# BoardB-USB.net
KiCad netlist of a schematic drawn in Altium Designer
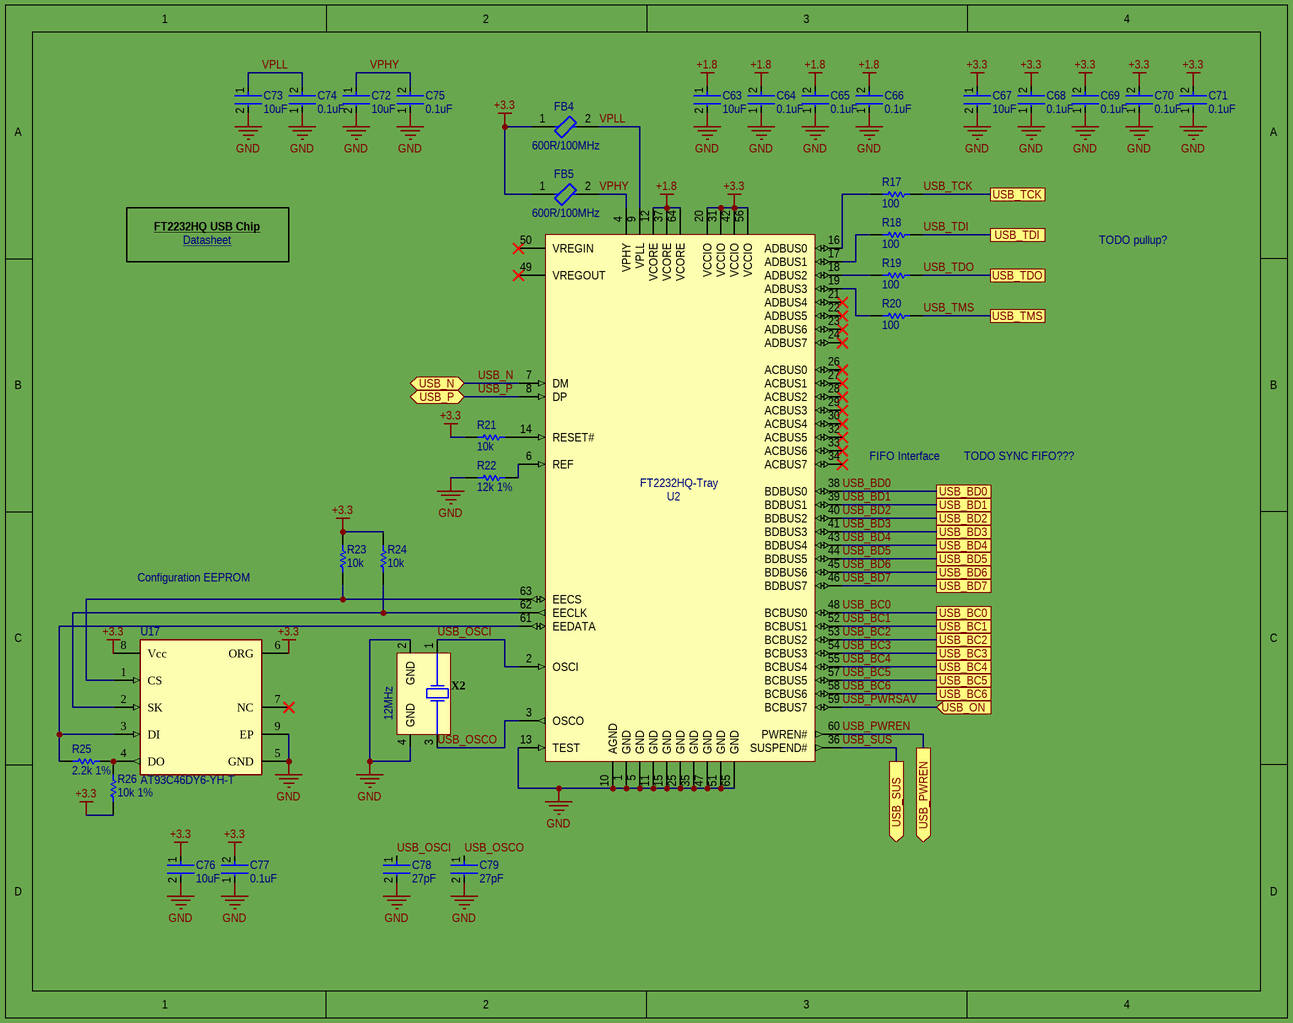
[diagram p0: BoardB-USB.SchDoc]

(export (version "E")
  (design (tool "Eeschema 10.0.6"))
  (components
    (comp (ref "C63")
      (value "10uF")
      (footprint "FP-CL05A106MP5NUNC-IPC_C")
      (description "CAP CER 10UF 10V X5R 0402")
      (fields
        (field (name "OCTOPART") "https://octopart.com/cl05a106mp5nunc-samsung-22457395")
        (field (name "TOLERANCE") "20%")
      )
      (libsource (lib "Altium Content Vault") (part "b4654b650e69147ec39a6b967a45e02"))
    )
    (comp (ref "C64")
      (value "0.1uF")
      (footprint "FP-GRM15-IPC_C")
      (description "CAP CER 0.1UF 16V X7R 0402")
      (fields (field (name "MANUFACTURER PART NUMBER") "GRM155R71C104KA88D") (field (name "TOLERANCE") "10%"))
      (libsource (lib "Altium Content Vault") (part "236180d848d6139a670b325ea6854c9"))
    )
    (comp (ref "C65")
      (value "0.1uF")
      (footprint "FP-GRM15-IPC_C")
      (description "CAP CER 0.1UF 16V X7R 0402")
      (fields (field (name "MANUFACTURER PART NUMBER") "GRM155R71C104KA88D") (field (name "TOLERANCE") "10%"))
      (libsource (lib "Altium Content Vault") (part "236180d848d6139a670b325ea6854c9"))
    )
    (comp (ref "C66")
      (value "0.1uF")
      (footprint "FP-GRM15-IPC_C")
      (description "CAP CER 0.1UF 16V X7R 0402")
      (fields (field (name "MANUFACTURER PART NUMBER") "GRM155R71C104KA88D") (field (name "TOLERANCE") "10%"))
      (libsource (lib "Altium Content Vault") (part "236180d848d6139a670b325ea6854c9"))
    )
    (comp (ref "C67")
      (value "10uF")
      (footprint "FP-CL05A106MP5NUNC-IPC_C")
      (description "CAP CER 10UF 10V X5R 0402")
      (fields
        (field (name "OCTOPART") "https://octopart.com/cl05a106mp5nunc-samsung-22457395")
        (field (name "TOLERANCE") "20%")
      )
      (libsource (lib "Altium Content Vault") (part "b4654b650e69147ec39a6b967a45e02"))
    )
    (comp (ref "C68")
      (value "0.1uF")
      (footprint "FP-GRM15-IPC_C")
      (description "CAP CER 0.1UF 16V X7R 0402")
      (fields (field (name "MANUFACTURER PART NUMBER") "GRM155R71C104KA88D") (field (name "TOLERANCE") "10%"))
      (libsource (lib "Altium Content Vault") (part "236180d848d6139a670b325ea6854c9"))
    )
    (comp (ref "C69")
      (value "0.1uF")
      (footprint "FP-GRM15-IPC_C")
      (description "CAP CER 0.1UF 16V X7R 0402")
      (fields (field (name "MANUFACTURER PART NUMBER") "GRM155R71C104KA88D") (field (name "TOLERANCE") "10%"))
      (libsource (lib "Altium Content Vault") (part "236180d848d6139a670b325ea6854c9"))
    )
    (comp (ref "C70")
      (value "0.1uF")
      (footprint "FP-GRM15-IPC_C")
      (description "CAP CER 0.1UF 16V X7R 0402")
      (fields (field (name "MANUFACTURER PART NUMBER") "GRM155R71C104KA88D") (field (name "TOLERANCE") "10%"))
      (libsource (lib "Altium Content Vault") (part "236180d848d6139a670b325ea6854c9"))
    )
    (comp (ref "C71")
      (value "0.1uF")
      (footprint "FP-GRM15-IPC_C")
      (description "CAP CER 0.1UF 16V X7R 0402")
      (fields (field (name "MANUFACTURER PART NUMBER") "GRM155R71C104KA88D") (field (name "TOLERANCE") "10%"))
      (libsource (lib "Altium Content Vault") (part "236180d848d6139a670b325ea6854c9"))
    )
    (comp (ref "C72")
      (value "10uF")
      (footprint "FP-CL05A106MP5NUNC-IPC_C")
      (description "CAP CER 10UF 10V X5R 0402")
      (fields
        (field (name "OCTOPART") "https://octopart.com/cl05a106mp5nunc-samsung-22457395")
        (field (name "TOLERANCE") "20%")
      )
      (libsource (lib "Altium Content Vault") (part "b4654b650e69147ec39a6b967a45e02"))
    )
    (comp (ref "C73")
      (value "10uF")
      (footprint "FP-CL05A106MP5NUNC-IPC_C")
      (description "CAP CER 10UF 10V X5R 0402")
      (fields
        (field (name "OCTOPART") "https://octopart.com/cl05a106mp5nunc-samsung-22457395")
        (field (name "TOLERANCE") "20%")
      )
      (libsource (lib "Altium Content Vault") (part "b4654b650e69147ec39a6b967a45e02"))
    )
    (comp (ref "C74")
      (value "0.1uF")
      (footprint "FP-GRM15-IPC_C")
      (description "CAP CER 0.1UF 16V X7R 0402")
      (fields (field (name "MANUFACTURER PART NUMBER") "GRM155R71C104KA88D") (field (name "TOLERANCE") "10%"))
      (libsource (lib "Altium Content Vault") (part "236180d848d6139a670b325ea6854c9"))
    )
    (comp (ref "C75")
      (value "0.1uF")
      (footprint "FP-GRM15-IPC_C")
      (description "CAP CER 0.1UF 16V X7R 0402")
      (fields (field (name "MANUFACTURER PART NUMBER") "GRM155R71C104KA88D") (field (name "TOLERANCE") "10%"))
      (libsource (lib "Altium Content Vault") (part "236180d848d6139a670b325ea6854c9"))
    )
    (comp (ref "C76")
      (value "10uF")
      (footprint "FP-CL05A106MP5NUNC-IPC_C")
      (description "CAP CER 10UF 10V X5R 0402")
      (fields
        (field (name "OCTOPART") "https://octopart.com/cl05a106mp5nunc-samsung-22457395")
        (field (name "TOLERANCE") "20%")
      )
      (libsource (lib "Altium Content Vault") (part "b4654b650e69147ec39a6b967a45e02"))
    )
    (comp (ref "C77")
      (value "0.1uF")
      (footprint "FP-GRM15-IPC_C")
      (description "CAP CER 0.1UF 16V X7R 0402")
      (fields (field (name "MANUFACTURER PART NUMBER") "GRM155R71C104KA88D") (field (name "TOLERANCE") "10%"))
      (libsource (lib "Altium Content Vault") (part "236180d848d6139a670b325ea6854c9"))
    )
    (comp (ref "C78")
      (value "27pF")
      (footprint "FP-C0402-BB-MFG")
      (description "CAP CER 27PF 50V C0G/NP0 0402")
      (fields (field (name "MANUFACTURER") "Kemet") (field (name "TOLERANCE") "0.05"))
      (libsource (lib "Altium Content Vault") (part "b4654b650e69147ec39a6b967a45e02"))
    )
    (comp (ref "C79")
      (value "27pF")
      (footprint "FP-C0402-BB-MFG")
      (description "CAP CER 27PF 50V C0G/NP0 0402")
      (fields (field (name "MANUFACTURER") "Kemet") (field (name "TOLERANCE") "0.05"))
      (libsource (lib "Altium Content Vault") (part "b4654b650e69147ec39a6b967a45e02"))
    )
    (comp (ref "FB4")
      (value "600R/100MHz")
      (footprint "FP-BLM18-0_15-t0_8-MFG")
      (description "Chip Ferrite Bead, 0603, 600Ω @ 100MHz, 0.38Ω, 25%, 500mA")
      (fields (field (name "TOLERANCE") "25%"))
      (libsource (lib "Altium Content Vault") (part "5f30dd21d616792df468990f7003faa"))
    )
    (comp (ref "FB5")
      (value "600R/100MHz")
      (footprint "FP-BLM18-0_15-t0_8-MFG")
      (description "Chip Ferrite Bead, 0603, 600Ω @ 100MHz, 0.38Ω, 25%, 500mA")
      (fields (field (name "TOLERANCE") "25%"))
      (libsource (lib "Altium Content Vault") (part "5f30dd21d616792df468990f7003faa"))
    )
    (comp (ref "R17")
      (value "100")
      (footprint "RESC1005X40X25LL05T10")
      (fields (field (name "PART NUMBER") "RC0402FR-07100RL") (field (name "MANUFACTURER") "Yageo / Phycomp"))
      (libsource (lib "Altium Content Vault") (part "RES"))
    )
    (comp (ref "R18")
      (value "100")
      (footprint "RESC1005X40X25LL05T10")
      (fields (field (name "PART NUMBER") "RC0402FR-07100RL") (field (name "MANUFACTURER") "Yageo / Phycomp"))
      (libsource (lib "Altium Content Vault") (part "RES"))
    )
    (comp (ref "R19")
      (value "100")
      (footprint "RESC1005X40X25LL05T10")
      (fields (field (name "PART NUMBER") "RC0402FR-07100RL") (field (name "MANUFACTURER") "Yageo / Phycomp"))
      (libsource (lib "Altium Content Vault") (part "RES"))
    )
    (comp (ref "R20")
      (value "100")
      (footprint "RESC1005X40X25LL05T10")
      (fields (field (name "PART NUMBER") "RC0402FR-07100RL") (field (name "MANUFACTURER") "Yageo / Phycomp"))
      (libsource (lib "Altium Content Vault") (part "RES"))
    )
    (comp (ref "R21")
      (value "10k")
      (footprint "RESC1005X40X25LL05T05")
      (description "Chip Resistor, 10 KOhm, +/- 1%, 0.1 W, -55 to 155 degC, 0402 (1005 Metric), RoHS, Tape and Reel")
      (fields (field (name "TOLERANCE") "1%") (field (name "MANUFACTURER") "Panasonic"))
      (libsource (lib "Altium Content Vault") (part "RES-2"))
    )
    (comp (ref "R22")
      (value "12k 1%")
      (footprint "RESC1005X40X25LL05T05")
      (description "Chip Resistor, 12 KOhm, +/- 1%, 0.1 W, -55 to 155 degC, 0402 (1005 Metric), RoHS, Tape and Reel")
      (fields (field (name "TOLERANCE") "1%") (field (name "PARTNUMBER") "ERJ-2RKF1202X"))
      (libsource (lib "Altium Content Vault") (part "RES-2"))
    )
    (comp (ref "R23")
      (value "10k")
      (footprint "RESC1005X40X25LL05T05")
      (description "Chip Resistor, 10 KOhm, +/- 1%, 0.1 W, -55 to 155 degC, 0402 (1005 Metric), RoHS, Tape and Reel")
      (fields (field (name "TOLERANCE") "1%") (field (name "MANUFACTURER") "Panasonic"))
      (libsource (lib "Altium Content Vault") (part "RES-2"))
    )
    (comp (ref "R24")
      (value "10k")
      (footprint "RESC1005X40X25LL05T05")
      (description "Chip Resistor, 10 KOhm, +/- 1%, 0.1 W, -55 to 155 degC, 0402 (1005 Metric), RoHS, Tape and Reel")
      (fields (field (name "TOLERANCE") "1%") (field (name "MANUFACTURER") "Panasonic"))
      (libsource (lib "Altium Content Vault") (part "RES-2"))
    )
    (comp (ref "R25")
      (value "2.2k 1%")
      (footprint "RESC1005X40X25NL05T10")
      (fields (field (name "MANUFACTURER") "Yageo / Phycomp") (field (name "PART NUMBER") "RC0402FR-072K2L"))
      (libsource (lib "Altium Content Vault") (part "RES"))
    )
    (comp (ref "R26")
      (value "10k 1%")
      (footprint "RESC1005X40X25LL05T05")
      (description "Chip Resistor, 10 KOhm, +/- 1%, 0.1 W, -55 to 155 degC, 0402 (1005 Metric), RoHS, Tape and Reel")
      (fields (field (name "TOLERANCE") "1%") (field (name "MANUFACTURER") "Panasonic"))
      (libsource (lib "Altium Content Vault") (part "RES-2"))
    )
    (comp (ref "U2")
      (value "FT2232HQ-Tray")
      (footprint "QFN64_2_N")
      (description "Dual High Speed USB To Multipurpose UART/FIFO IC, 64-pin QFN, Tray")
      (fields (field (name "MANUFACTURER") "FTDI"))
      (libsource (lib "Altium Content Vault") (part "COM-UART-FT2232H-QFN64"))
    )
    (comp (ref "U17")
      (value "AT93C46DY6-YH-T")
      (footprint "FP-C04-21355-Q4B-IPC_C")
      (description "IC EEPROM 1KBIT SPI 8MINI MAP")
      (libsource (lib "Altium Content Vault") (part "38d5b16ef365a7a64ac37fa7d10f17c"))
    )
    (comp (ref "X2")
      (value "ABM8G-12.000MHZ-4Y-T3")
      (footprint "ABM8G-12.000MHZ-4Y-T3")
      (description "ABRACON - ABM8G-12.000MHZ-4Y-T3 - CRYSTAL, 12MHZ, 10PF, 3.2 X 2.5MM")
      (fields (field (name "MANUFACTURER") "Abracon"))
      (libsource (lib "Virtex") (part "ABM8G-12.000MHZ-4Y-T3"))
    )
  )
  (nets
    (net (code "1") (name "+1.8") (class "Default")
      (node (ref "C63") (pin "1") (pinfunction "1_1") (pintype "passive"))
      (node (ref "C64") (pin "2") (pinfunction "2_2") (pintype "passive"))
      (node (ref "C65") (pin "2") (pinfunction "2_2") (pintype "passive"))
      (node (ref "C66") (pin "2") (pinfunction "2_2") (pintype "passive"))
      (node (ref "U2") (pin "12") (pinfunction "VCORE_12") (pintype "power_in"))
      (node (ref "U2") (pin "37") (pinfunction "VCORE_37") (pintype "power_in"))
      (node (ref "U2") (pin "64") (pinfunction "VCORE_64") (pintype "power_in"))
    )
    (net (code "2") (name "+3.3") (class "Default")
      (node (ref "C67") (pin "1") (pinfunction "1_1") (pintype "passive"))
      (node (ref "C68") (pin "2") (pinfunction "2_2") (pintype "passive"))
      (node (ref "C69") (pin "2") (pinfunction "2_2") (pintype "passive"))
      (node (ref "C70") (pin "2") (pinfunction "2_2") (pintype "passive"))
      (node (ref "C71") (pin "2") (pinfunction "2_2") (pintype "passive"))
      (node (ref "C76") (pin "1") (pinfunction "1_1") (pintype "passive"))
      (node (ref "C77") (pin "2") (pinfunction "2_2") (pintype "passive"))
      (node (ref "FB4") (pin "1") (pinfunction "1_1") (pintype "passive"))
      (node (ref "FB5") (pin "1") (pinfunction "1_1") (pintype "passive"))
      (node (ref "R21") (pin "2") (pinfunction "2_2") (pintype "passive"))
      (node (ref "R23") (pin "2") (pinfunction "2_2") (pintype "passive"))
      (node (ref "R24") (pin "2") (pinfunction "2_2") (pintype "passive"))
      (node (ref "R26") (pin "1") (pinfunction "1_1") (pintype "passive"))
      (node (ref "U17") (pin "6") (pinfunction "ORG_6") (pintype "passive"))
      (node (ref "U17") (pin "8") (pinfunction "Vcc_8") (pintype "power_in"))
      (node (ref "U2") (pin "20") (pinfunction "VCCIO_20") (pintype "power_in"))
      (node (ref "U2") (pin "31") (pinfunction "VCCIO_31") (pintype "power_in"))
      (node (ref "U2") (pin "42") (pinfunction "VCCIO_42") (pintype "power_in"))
      (node (ref "U2") (pin "56") (pinfunction "VCCIO_56") (pintype "power_in"))
    )
    (net (code "3") (name "/USB_BC0") (class "Default")
      (node (ref "U2") (pin "48") (pinfunction "BCBUS0_48") (pintype "bidirectional"))
    )
    (net (code "4") (name "/USB_BC1") (class "Default")
      (node (ref "U2") (pin "52") (pinfunction "BCBUS1_52") (pintype "bidirectional"))
    )
    (net (code "5") (name "/USB_BC2") (class "Default")
      (node (ref "U2") (pin "53") (pinfunction "BCBUS2_53") (pintype "bidirectional"))
    )
    (net (code "6") (name "/USB_BC3") (class "Default")
      (node (ref "U2") (pin "54") (pinfunction "BCBUS3_54") (pintype "bidirectional"))
    )
    (net (code "7") (name "/USB_BC4") (class "Default")
      (node (ref "U2") (pin "55") (pinfunction "BCBUS4_55") (pintype "bidirectional"))
    )
    (net (code "8") (name "/USB_BC5") (class "Default")
      (node (ref "U2") (pin "57") (pinfunction "BCBUS5_57") (pintype "bidirectional"))
    )
    (net (code "9") (name "/USB_BC6") (class "Default")
      (node (ref "U2") (pin "58") (pinfunction "BCBUS6_58") (pintype "bidirectional"))
    )
    (net (code "10") (name "/USB_BD0") (class "Default")
      (node (ref "U2") (pin "38") (pinfunction "BDBUS0_38") (pintype "bidirectional"))
    )
    (net (code "11") (name "/USB_BD1") (class "Default")
      (node (ref "U2") (pin "39") (pinfunction "BDBUS1_39") (pintype "bidirectional"))
    )
    (net (code "12") (name "/USB_BD2") (class "Default")
      (node (ref "U2") (pin "40") (pinfunction "BDBUS2_40") (pintype "bidirectional"))
    )
    (net (code "13") (name "/USB_BD3") (class "Default")
      (node (ref "U2") (pin "41") (pinfunction "BDBUS3_41") (pintype "bidirectional"))
    )
    (net (code "14") (name "/USB_BD4") (class "Default")
      (node (ref "U2") (pin "43") (pinfunction "BDBUS4_43") (pintype "bidirectional"))
    )
    (net (code "15") (name "/USB_BD5") (class "Default")
      (node (ref "U2") (pin "44") (pinfunction "BDBUS5_44") (pintype "bidirectional"))
    )
    (net (code "16") (name "/USB_BD6") (class "Default")
      (node (ref "U2") (pin "45") (pinfunction "BDBUS6_45") (pintype "bidirectional"))
    )
    (net (code "17") (name "/USB_BD7") (class "Default")
      (node (ref "U2") (pin "46") (pinfunction "BDBUS7_46") (pintype "bidirectional"))
    )
    (net (code "18") (name "/USB_N") (class "Default")
      (node (ref "U2") (pin "7") (pinfunction "DM_7") (pintype "input"))
    )
    (net (code "19") (name "/USB_OSCI") (class "Default")
      (node (ref "C78") (pin "1") (pinfunction "1_1") (pintype "passive"))
      (node (ref "U2") (pin "2") (pinfunction "OSCI_2") (pintype "input"))
      (node (ref "X2") (pin "1") (pintype "passive"))
    )
    (net (code "20") (name "/USB_OSCO") (class "Default")
      (node (ref "C79") (pin "1") (pinfunction "1_1") (pintype "passive"))
      (node (ref "U2") (pin "3") (pinfunction "OSCO_3") (pintype "output"))
      (node (ref "X2") (pin "3") (pintype "passive"))
    )
    (net (code "21") (name "/USB_P") (class "Default")
      (node (ref "U2") (pin "8") (pinfunction "DP_8") (pintype "input"))
    )
    (net (code "22") (name "/USB_PWREN") (class "Default")
      (node (ref "U2") (pin "60") (pinfunction "PWREN#_60") (pintype "output"))
    )
    (net (code "23") (name "/USB_PWRSAV") (class "Default")
      (node (ref "U2") (pin "59") (pinfunction "BCBUS7_59") (pintype "bidirectional"))
    )
    (net (code "24") (name "/USB_SUS") (class "Default")
      (node (ref "U2") (pin "36") (pinfunction "SUSPEND#_36") (pintype "output"))
    )
    (net (code "25") (name "/USB_TCK") (class "Default")
      (node (ref "R17") (pin "2") (pinfunction "2_2") (pintype "passive"))
    )
    (net (code "26") (name "/USB_TDI") (class "Default")
      (node (ref "R18") (pin "2") (pinfunction "2_2") (pintype "passive"))
    )
    (net (code "27") (name "/USB_TDO") (class "Default")
      (node (ref "R19") (pin "2") (pinfunction "2_2") (pintype "passive"))
    )
    (net (code "28") (name "/USB_TMS") (class "Default")
      (node (ref "R20") (pin "2") (pinfunction "2_2") (pintype "passive"))
    )
    (net (code "29") (name "/VPHY") (class "Default")
      (node (ref "C72") (pin "1") (pinfunction "1_1") (pintype "passive"))
      (node (ref "C75") (pin "2") (pinfunction "2_2") (pintype "passive"))
      (node (ref "FB5") (pin "2") (pinfunction "2_2") (pintype "passive"))
      (node (ref "U2") (pin "4") (pinfunction "VPHY_4") (pintype "power_in"))
    )
    (net (code "30") (name "/VPLL") (class "Default")
      (node (ref "C73") (pin "1") (pinfunction "1_1") (pintype "passive"))
      (node (ref "C74") (pin "2") (pinfunction "2_2") (pintype "passive"))
      (node (ref "FB4") (pin "2") (pinfunction "2_2") (pintype "passive"))
      (node (ref "U2") (pin "9") (pinfunction "VPLL_9") (pintype "power_in"))
    )
    (net (code "31") (name "GND") (class "Default")
      (node (ref "C63") (pin "2") (pinfunction "2_2") (pintype "passive"))
      (node (ref "C64") (pin "1") (pinfunction "1_1") (pintype "passive"))
      (node (ref "C65") (pin "1") (pinfunction "1_1") (pintype "passive"))
      (node (ref "C66") (pin "1") (pinfunction "1_1") (pintype "passive"))
      (node (ref "C67") (pin "2") (pinfunction "2_2") (pintype "passive"))
      (node (ref "C68") (pin "1") (pinfunction "1_1") (pintype "passive"))
      (node (ref "C69") (pin "1") (pinfunction "1_1") (pintype "passive"))
      (node (ref "C70") (pin "1") (pinfunction "1_1") (pintype "passive"))
      (node (ref "C71") (pin "1") (pinfunction "1_1") (pintype "passive"))
      (node (ref "C72") (pin "2") (pinfunction "2_2") (pintype "passive"))
      (node (ref "C73") (pin "2") (pinfunction "2_2") (pintype "passive"))
      (node (ref "C74") (pin "1") (pinfunction "1_1") (pintype "passive"))
      (node (ref "C75") (pin "1") (pinfunction "1_1") (pintype "passive"))
      (node (ref "C76") (pin "2") (pinfunction "2_2") (pintype "passive"))
      (node (ref "C77") (pin "1") (pinfunction "1_1") (pintype "passive"))
      (node (ref "C78") (pin "2") (pinfunction "2_2") (pintype "passive"))
      (node (ref "C79") (pin "2") (pinfunction "2_2") (pintype "passive"))
      (node (ref "R22") (pin "1") (pinfunction "1_1") (pintype "passive"))
      (node (ref "U17") (pin "5") (pinfunction "GND_5") (pintype "power_in"))
      (node (ref "U17") (pin "9") (pinfunction "EP_9") (pintype "passive"))
      (node (ref "U2") (pin "1") (pinfunction "GND_1") (pintype "power_in"))
      (node (ref "U2") (pin "10") (pinfunction "AGND_10") (pintype "power_in"))
      (node (ref "U2") (pin "11") (pinfunction "GND_11") (pintype "power_in"))
      (node (ref "U2") (pin "13") (pinfunction "TEST_13") (pintype "input"))
      (node (ref "U2") (pin "15") (pinfunction "GND_15") (pintype "power_in"))
      (node (ref "U2") (pin "25") (pinfunction "GND_25") (pintype "power_in"))
      (node (ref "U2") (pin "35") (pinfunction "GND_35") (pintype "power_in"))
      (node (ref "U2") (pin "47") (pinfunction "GND_47") (pintype "power_in"))
      (node (ref "U2") (pin "5") (pinfunction "GND_5") (pintype "power_in"))
      (node (ref "U2") (pin "51") (pinfunction "GND_51") (pintype "power_in"))
      (node (ref "U2") (pin "65") (pinfunction "GND_65") (pintype "power_in"))
      (node (ref "X2") (pin "2") (pinfunction "GND_2") (pintype "power_in"))
      (node (ref "X2") (pin "4") (pinfunction "GND_4") (pintype "power_in"))
    )
    (net (code "32") (name "Net-(U2-ADBUS0)") (class "Default")
      (node (ref "R17") (pin "1") (pinfunction "1_1") (pintype "passive"))
      (node (ref "U2") (pin "16") (pinfunction "ADBUS0_16") (pintype "bidirectional"))
    )
    (net (code "33") (name "Net-(U2-ADBUS1)") (class "Default")
      (node (ref "R18") (pin "1") (pinfunction "1_1") (pintype "passive"))
      (node (ref "U2") (pin "17") (pinfunction "ADBUS1_17") (pintype "bidirectional"))
    )
    (net (code "34") (name "Net-(U2-ADBUS2)") (class "Default")
      (node (ref "R19") (pin "1") (pinfunction "1_1") (pintype "passive"))
      (node (ref "U2") (pin "18") (pinfunction "ADBUS2_18") (pintype "bidirectional"))
    )
    (net (code "35") (name "Net-(U2-ADBUS3)") (class "Default")
      (node (ref "R20") (pin "1") (pinfunction "1_1") (pintype "passive"))
      (node (ref "U2") (pin "19") (pinfunction "ADBUS3_19") (pintype "bidirectional"))
    )
    (net (code "36") (name "Net-(U2-REF)") (class "Default")
      (node (ref "R22") (pin "2") (pinfunction "2_2") (pintype "passive"))
      (node (ref "U2") (pin "6") (pinfunction "REF_6") (pintype "input"))
    )
    (net (code "37") (name "Net-(U2-RESET#)") (class "Default")
      (node (ref "R21") (pin "1") (pinfunction "1_1") (pintype "passive"))
      (node (ref "U2") (pin "14") (pinfunction "RESET#_14") (pintype "input"))
    )
    (net (code "38") (name "Net-(U17-CS)") (class "Default")
      (node (ref "R23") (pin "1") (pinfunction "1_1") (pintype "passive"))
      (node (ref "U17") (pin "1") (pinfunction "CS_1") (pintype "input"))
      (node (ref "U2") (pin "63") (pinfunction "EECS_63") (pintype "bidirectional"))
    )
    (net (code "39") (name "Net-(U17-DI)") (class "Default")
      (node (ref "R25") (pin "1") (pinfunction "1_1") (pintype "passive"))
      (node (ref "U17") (pin "3") (pinfunction "DI_3") (pintype "input"))
      (node (ref "U2") (pin "61") (pinfunction "EEDATA_61") (pintype "bidirectional"))
    )
    (net (code "40") (name "Net-(U17-DO)") (class "Default")
      (node (ref "R25") (pin "2") (pinfunction "2_2") (pintype "passive"))
      (node (ref "R26") (pin "2") (pinfunction "2_2") (pintype "passive"))
      (node (ref "U17") (pin "4") (pinfunction "DO_4") (pintype "output"))
    )
    (net (code "41") (name "Net-(U17-SK)") (class "Default")
      (node (ref "R24") (pin "1") (pinfunction "1_1") (pintype "passive"))
      (node (ref "U17") (pin "2") (pinfunction "SK_2") (pintype "input"))
      (node (ref "U2") (pin "62") (pinfunction "EECLK_62") (pintype "output"))
    )
    (net (code "42") (name "unconnected-(U2-ACBUS0-Pad26)") (class "Default")
      (node (ref "U2") (pin "26") (pinfunction "ACBUS0_26") (pintype "bidirectional+no_connect"))
    )
    (net (code "43") (name "unconnected-(U2-ACBUS1-Pad27)") (class "Default")
      (node (ref "U2") (pin "27") (pinfunction "ACBUS1_27") (pintype "bidirectional+no_connect"))
    )
    (net (code "44") (name "unconnected-(U2-ACBUS2-Pad28)") (class "Default")
      (node (ref "U2") (pin "28") (pinfunction "ACBUS2_28") (pintype "bidirectional+no_connect"))
    )
    (net (code "45") (name "unconnected-(U2-ACBUS3-Pad29)") (class "Default")
      (node (ref "U2") (pin "29") (pinfunction "ACBUS3_29") (pintype "bidirectional+no_connect"))
    )
    (net (code "46") (name "unconnected-(U2-ACBUS4-Pad30)") (class "Default")
      (node (ref "U2") (pin "30") (pinfunction "ACBUS4_30") (pintype "bidirectional+no_connect"))
    )
    (net (code "47") (name "unconnected-(U2-ACBUS5-Pad32)") (class "Default")
      (node (ref "U2") (pin "32") (pinfunction "ACBUS5_32") (pintype "bidirectional+no_connect"))
    )
    (net (code "48") (name "unconnected-(U2-ACBUS6-Pad33)") (class "Default")
      (node (ref "U2") (pin "33") (pinfunction "ACBUS6_33") (pintype "bidirectional+no_connect"))
    )
    (net (code "49") (name "unconnected-(U2-ACBUS7-Pad34)") (class "Default")
      (node (ref "U2") (pin "34") (pinfunction "ACBUS7_34") (pintype "bidirectional+no_connect"))
    )
    (net (code "50") (name "unconnected-(U2-ADBUS4-Pad21)") (class "Default")
      (node (ref "U2") (pin "21") (pinfunction "ADBUS4_21") (pintype "bidirectional+no_connect"))
    )
    (net (code "51") (name "unconnected-(U2-ADBUS5-Pad22)") (class "Default")
      (node (ref "U2") (pin "22") (pinfunction "ADBUS5_22") (pintype "bidirectional+no_connect"))
    )
    (net (code "52") (name "unconnected-(U2-ADBUS6-Pad23)") (class "Default")
      (node (ref "U2") (pin "23") (pinfunction "ADBUS6_23") (pintype "bidirectional+no_connect"))
    )
    (net (code "53") (name "unconnected-(U2-ADBUS7-Pad24)") (class "Default")
      (node (ref "U2") (pin "24") (pinfunction "ADBUS7_24") (pintype "bidirectional+no_connect"))
    )
    (net (code "54") (name "unconnected-(U2-VREGIN-Pad50)") (class "Default")
      (node (ref "U2") (pin "50") (pinfunction "VREGIN_50") (pintype "power_in+no_connect"))
    )
    (net (code "55") (name "unconnected-(U2-VREGOUT-Pad49)") (class "Default")
      (node (ref "U2") (pin "49") (pinfunction "VREGOUT_49") (pintype "power_in+no_connect"))
    )
    (net (code "56") (name "unconnected-(U17-NC-Pad7)") (class "Default")
      (node (ref "U17") (pin "7") (pinfunction "NC_7") (pintype "passive+no_connect"))
    )
  )
)
